# schematic.net
KiCad netlist of a schematic drawn in EAGLE
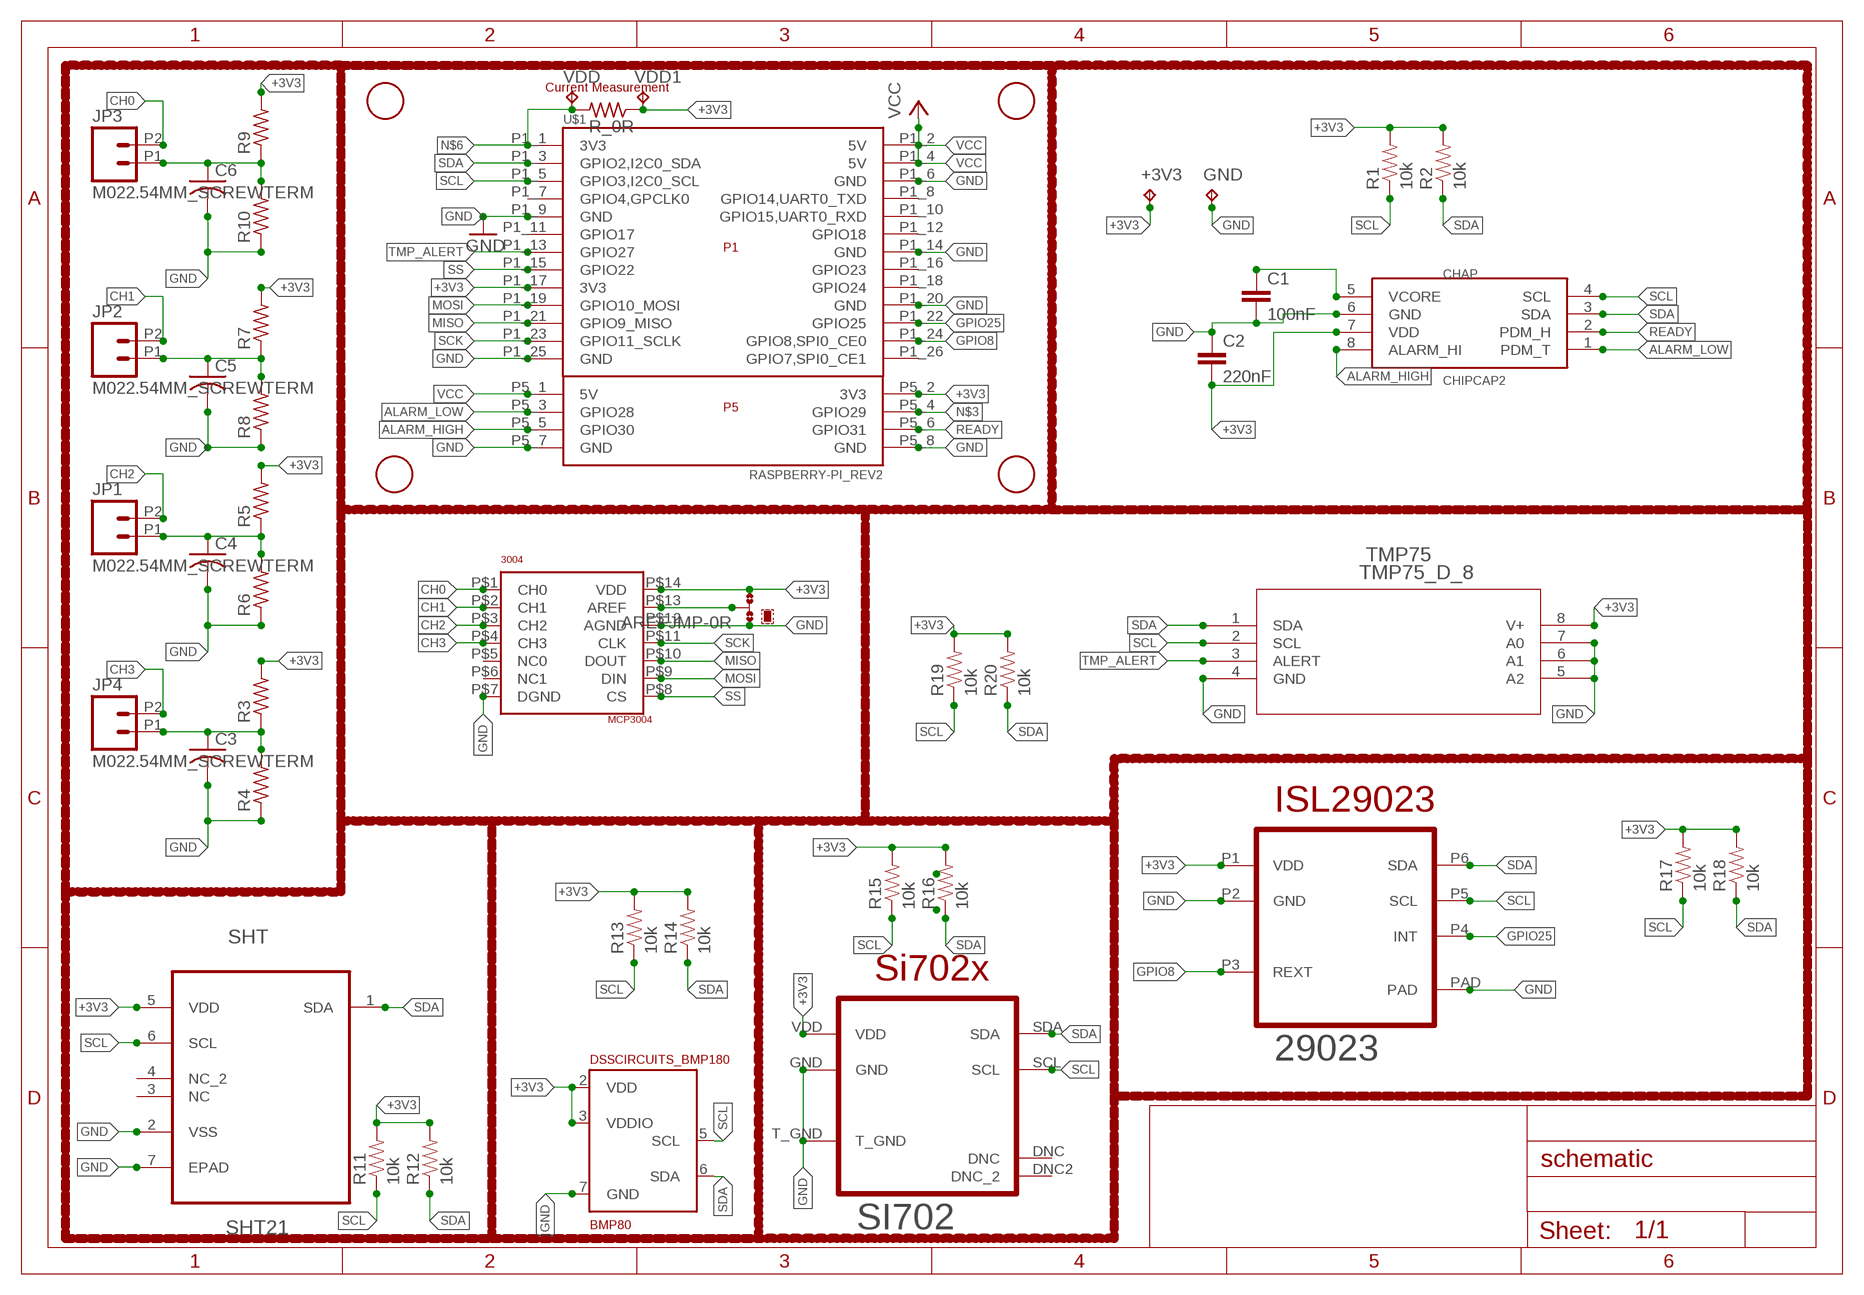
[diagram p0: schematic, sheet 1]

(export (version "E")
  (design (tool "Eeschema 10.0.6"))
  (components
    (comp (ref "+3V3")
      (value "TPTP20R")
      (footprint "eagle-import:TP20R")
      (libsource (lib "eagle-import") (part "TPTP20R"))
    )
    (comp (ref "3004")
      (value "MCP3004")
      (footprint "eagle-import:TSSOP14_4MM4")
      (libsource (lib "eagle-import") (part "MCP3004"))
    )
    (comp (ref "29023")
      (value "ISL29023")
      (footprint "eagle-import:ODFN6")
      (libsource (lib "eagle-import") (part "ISL29023"))
    )
    (comp (ref "AREFJMP")
      (value "0R-JUMPA")
      (footprint "eagle-import:A0R-JMP")
      (libsource (lib "eagle-import") (part "0R-JUMPA"))
    )
    (comp (ref "BMP80")
      (value "DSSCIRCUITS_BMP180")
      (footprint "eagle-import:DSSCIRCUITS_LGA7")
      (libsource (lib "eagle-import") (part "DSSCIRCUITS_BMP180"))
    )
    (comp (ref "C1")
      (value "100nF")
      (footprint "eagle-import:0402-CAP")
      (libsource (lib "eagle-import") (part "CAP0402-CAP"))
    )
    (comp (ref "C2")
      (value "220nF")
      (footprint "eagle-import:0402-CAP")
      (libsource (lib "eagle-import") (part "CAP0402-CAP"))
    )
    (comp (ref "C3")
      (value "C-USC0402")
      (footprint "eagle-import:C0402")
      (libsource (lib "eagle-import") (part "C-USC0402"))
    )
    (comp (ref "C4")
      (value "C-USC0402")
      (footprint "eagle-import:C0402")
      (libsource (lib "eagle-import") (part "C-USC0402"))
    )
    (comp (ref "C5")
      (value "C-USC0402")
      (footprint "eagle-import:C0402")
      (libsource (lib "eagle-import") (part "C-USC0402"))
    )
    (comp (ref "C6")
      (value "C-USC0402")
      (footprint "eagle-import:C0402")
      (libsource (lib "eagle-import") (part "C-USC0402"))
    )
    (comp (ref "CHAP")
      (value "CHIPCAP2")
      (footprint "eagle-import:CHIPCAP2")
      (libsource (lib "eagle-import") (part "CHIPCAP2"))
    )
    (comp (ref "GND")
      (value "TPTP20R")
      (footprint "eagle-import:TP20R")
      (libsource (lib "eagle-import") (part "TPTP20R"))
    )
    (comp (ref "JP1")
      (value "M022.54MM_SCREWTERM")
      (footprint "eagle-import:1X02_2.54_SCREWTERM")
      (libsource (lib "eagle-import") (part "M022.54MM_SCREWTERM"))
    )
    (comp (ref "JP2")
      (value "M022.54MM_SCREWTERM")
      (footprint "eagle-import:1X02_2.54_SCREWTERM")
      (libsource (lib "eagle-import") (part "M022.54MM_SCREWTERM"))
    )
    (comp (ref "JP3")
      (value "M022.54MM_SCREWTERM")
      (footprint "eagle-import:1X02_2.54_SCREWTERM")
      (libsource (lib "eagle-import") (part "M022.54MM_SCREWTERM"))
    )
    (comp (ref "JP4")
      (value "M022.54MM_SCREWTERM")
      (footprint "eagle-import:1X02_2.54_SCREWTERM")
      (libsource (lib "eagle-import") (part "M022.54MM_SCREWTERM"))
    )
    (comp (ref "R1")
      (value "10k")
      (footprint "eagle-import:0603-RES")
      (libsource (lib "eagle-import") (part "RESISTOR0603"))
    )
    (comp (ref "R2")
      (value "10k")
      (footprint "eagle-import:0603-RES")
      (libsource (lib "eagle-import") (part "RESISTOR0603"))
    )
    (comp (ref "R3")
      (value "R-US_R0402")
      (footprint "eagle-import:R0402")
      (libsource (lib "eagle-import") (part "R-US_R0402"))
    )
    (comp (ref "R4")
      (value "R-US_R0402")
      (footprint "eagle-import:R0402")
      (libsource (lib "eagle-import") (part "R-US_R0402"))
    )
    (comp (ref "R5")
      (value "R-US_R0402")
      (footprint "eagle-import:R0402")
      (libsource (lib "eagle-import") (part "R-US_R0402"))
    )
    (comp (ref "R6")
      (value "R-US_R0402")
      (footprint "eagle-import:R0402")
      (libsource (lib "eagle-import") (part "R-US_R0402"))
    )
    (comp (ref "R7")
      (value "R-US_R0402")
      (footprint "eagle-import:R0402")
      (libsource (lib "eagle-import") (part "R-US_R0402"))
    )
    (comp (ref "R8")
      (value "R-US_R0402")
      (footprint "eagle-import:R0402")
      (libsource (lib "eagle-import") (part "R-US_R0402"))
    )
    (comp (ref "R9")
      (value "R-US_R0402")
      (footprint "eagle-import:R0402")
      (libsource (lib "eagle-import") (part "R-US_R0402"))
    )
    (comp (ref "R10")
      (value "R-US_R0402")
      (footprint "eagle-import:R0402")
      (libsource (lib "eagle-import") (part "R-US_R0402"))
    )
    (comp (ref "R11")
      (value "10k")
      (footprint "eagle-import:0603-RES")
      (libsource (lib "eagle-import") (part "RESISTOR0603"))
    )
    (comp (ref "R12")
      (value "10k")
      (footprint "eagle-import:0603-RES")
      (libsource (lib "eagle-import") (part "RESISTOR0603"))
    )
    (comp (ref "R13")
      (value "10k")
      (footprint "eagle-import:0603-RES")
      (libsource (lib "eagle-import") (part "RESISTOR0603"))
    )
    (comp (ref "R14")
      (value "10k")
      (footprint "eagle-import:0603-RES")
      (libsource (lib "eagle-import") (part "RESISTOR0603"))
    )
    (comp (ref "R15")
      (value "10k")
      (footprint "eagle-import:0603-RES")
      (libsource (lib "eagle-import") (part "RESISTOR0603"))
    )
    (comp (ref "R16")
      (value "10k")
      (footprint "eagle-import:0603-RES")
      (libsource (lib "eagle-import") (part "RESISTOR0603"))
    )
    (comp (ref "R17")
      (value "10k")
      (footprint "eagle-import:0603-RES")
      (libsource (lib "eagle-import") (part "RESISTOR0603"))
    )
    (comp (ref "R18")
      (value "10k")
      (footprint "eagle-import:0603-RES")
      (libsource (lib "eagle-import") (part "RESISTOR0603"))
    )
    (comp (ref "R19")
      (value "10k")
      (footprint "eagle-import:0603-RES")
      (libsource (lib "eagle-import") (part "RESISTOR0603"))
    )
    (comp (ref "R20")
      (value "10k")
      (footprint "eagle-import:0603-RES")
      (libsource (lib "eagle-import") (part "RESISTOR0603"))
    )
    (comp (ref "R_0R")
      (value "R-US_R0402")
      (footprint "eagle-import:R0402")
      (libsource (lib "eagle-import") (part "R-US_R0402"))
    )
    (comp (ref "SHT")
      (value "SHT21")
      (footprint "eagle-import:DFN300X300X110-7N")
      (libsource (lib "eagle-import") (part "SHT21"))
    )
    (comp (ref "SI702")
      (value "SI702X")
      (footprint "eagle-import:DFN6")
      (libsource (lib "eagle-import") (part "SI702X"))
    )
    (comp (ref "TMP75")
      (value "TMP75_D_8")
      (footprint "eagle-import:D8")
      (fields
        (field (name "GENERIC_PART_NUMBER") "TMP75")
        (field (name "MANUFACTURER") "Texas Instruments")
        (field (name "MANUFACTURER_PART_NUMBER") "tmp75_d_8")
      )
      (libsource (lib "eagle-import") (part "TMP75_D_8"))
    )
    (comp (ref "U$1")
      (value "RASPBERRY-PI_REV2")
      (footprint "eagle-import:RASPBERRY-PI_REV2")
      (libsource (lib "eagle-import") (part "RASPBERRY-PI_REV2"))
    )
    (comp (ref "U$2")
      (value "FIDUCIAL")
      (footprint "eagle-import:FIDUCIAL_1MM")
      (libsource (lib "eagle-import") (part "FIDUCIAL"))
    )
    (comp (ref "U$3")
      (value "FIDUCIAL")
      (footprint "eagle-import:FIDUCIAL_1MM")
      (libsource (lib "eagle-import") (part "FIDUCIAL"))
    )
    (comp (ref "U$4")
      (value "FIDUCIAL")
      (footprint "eagle-import:FIDUCIAL_1MM")
      (libsource (lib "eagle-import") (part "FIDUCIAL"))
    )
    (comp (ref "U$5")
      (value "FIDUCIAL")
      (footprint "eagle-import:FIDUCIAL_1MM")
      (libsource (lib "eagle-import") (part "FIDUCIAL"))
    )
    (comp (ref "VDD")
      (value "TPTP20R")
      (footprint "eagle-import:TP20R")
      (libsource (lib "eagle-import") (part "TPTP20R"))
    )
    (comp (ref "VDD1")
      (value "TPTP20R")
      (footprint "eagle-import:TP20R")
      (libsource (lib "eagle-import") (part "TPTP20R"))
    )
  )
  (nets
    (net (code "1") (name "+3V3") (class "Default")
      (node (ref "+3V3") (pin "TP") (pinfunction "TP_TP") (pintype "input"))
      (node (ref "29023") (pin "P1") (pinfunction "VDD_P1") (pintype "bidirectional"))
      (node (ref "3004") (pin "P$14") (pinfunction "VDD_P$14") (pintype "bidirectional"))
      (node (ref "AREFJMP") (pin "3") (pinfunction "3_3") (pintype "passive"))
      (node (ref "BMP80") (pin "2") (pinfunction "VDD_2") (pintype "power_in"))
      (node (ref "BMP80") (pin "3") (pinfunction "VDDIO_3") (pintype "power_in"))
      (node (ref "C2") (pin "2") (pinfunction "2_2") (pintype "passive"))
      (node (ref "CHAP") (pin "7") (pinfunction "VDD_7") (pintype "bidirectional"))
      (node (ref "R1") (pin "2") (pinfunction "2_2") (pintype "passive"))
      (node (ref "R11") (pin "2") (pinfunction "2_2") (pintype "passive"))
      (node (ref "R12") (pin "2") (pinfunction "2_2") (pintype "passive"))
      (node (ref "R13") (pin "2") (pinfunction "2_2") (pintype "passive"))
      (node (ref "R14") (pin "2") (pinfunction "2_2") (pintype "passive"))
      (node (ref "R15") (pin "2") (pinfunction "2_2") (pintype "passive"))
      (node (ref "R16") (pin "2") (pinfunction "2_2") (pintype "passive"))
      (node (ref "R17") (pin "2") (pinfunction "2_2") (pintype "passive"))
      (node (ref "R18") (pin "2") (pinfunction "2_2") (pintype "passive"))
      (node (ref "R19") (pin "2") (pinfunction "2_2") (pintype "passive"))
      (node (ref "R2") (pin "2") (pinfunction "2_2") (pintype "passive"))
      (node (ref "R20") (pin "2") (pinfunction "2_2") (pintype "passive"))
      (node (ref "R3") (pin "2") (pinfunction "2_2") (pintype "passive"))
      (node (ref "R5") (pin "2") (pinfunction "2_2") (pintype "passive"))
      (node (ref "R7") (pin "2") (pinfunction "2_2") (pintype "passive"))
      (node (ref "R9") (pin "2") (pinfunction "2_2") (pintype "passive"))
      (node (ref "R_0R") (pin "1") (pinfunction "1_1") (pintype "passive"))
      (node (ref "SHT") (pin "5") (pinfunction "VDD_5") (pintype "power_in"))
      (node (ref "SI702") (pin "VDD") (pinfunction "VDD_VDD") (pintype "bidirectional"))
      (node (ref "TMP75") (pin "8") (pinfunction "V+_8") (pintype "power_in"))
      (node (ref "U$1") (pin "P1_17") (pinfunction "3V3_P1_17") (pintype "bidirectional"))
      (node (ref "U$1") (pin "P5_2") (pinfunction "3V3_P5_2") (pintype "bidirectional"))
      (node (ref "VDD1") (pin "TP") (pinfunction "TP_TP") (pintype "input"))
    )
    (net (code "2") (name "ALARM_HIGH") (class "Default")
      (node (ref "CHAP") (pin "8") (pinfunction "ALARM_HI_8") (pintype "bidirectional"))
      (node (ref "U$1") (pin "P5_5") (pinfunction "GPIO30_P5_5") (pintype "bidirectional"))
    )
    (net (code "3") (name "ALARM_LOW") (class "Default")
      (node (ref "CHAP") (pin "1") (pinfunction "PDM_T_1") (pintype "bidirectional"))
      (node (ref "U$1") (pin "P5_3") (pinfunction "GPIO28_P5_3") (pintype "bidirectional"))
    )
    (net (code "4") (name "CH0") (class "Default")
      (node (ref "3004") (pin "P$1") (pinfunction "CH0_P$1") (pintype "bidirectional"))
      (node (ref "JP3") (pin "P2") (pinfunction "2_P2") (pintype "passive"))
    )
    (net (code "5") (name "CH1") (class "Default")
      (node (ref "3004") (pin "P$2") (pinfunction "CH1_P$2") (pintype "bidirectional"))
      (node (ref "JP2") (pin "P2") (pinfunction "2_P2") (pintype "passive"))
    )
    (net (code "6") (name "CH2") (class "Default")
      (node (ref "3004") (pin "P$3") (pinfunction "CH2_P$3") (pintype "bidirectional"))
      (node (ref "JP1") (pin "P2") (pinfunction "2_P2") (pintype "passive"))
    )
    (net (code "7") (name "CH3") (class "Default")
      (node (ref "3004") (pin "P$4") (pinfunction "CH3_P$4") (pintype "bidirectional"))
      (node (ref "JP4") (pin "P2") (pinfunction "2_P2") (pintype "passive"))
    )
    (net (code "8") (name "GND") (class "Default")
      (node (ref "29023") (pin "P2") (pinfunction "GND_P2") (pintype "bidirectional"))
      (node (ref "29023") (pin "PAD") (pinfunction "PAD_PAD") (pintype "bidirectional"))
      (node (ref "3004") (pin "P$12") (pinfunction "AGND_P$12") (pintype "bidirectional"))
      (node (ref "3004") (pin "P$7") (pinfunction "DGND_P$7") (pintype "bidirectional"))
      (node (ref "AREFJMP") (pin "1") (pinfunction "1_1") (pintype "passive"))
      (node (ref "BMP80") (pin "7") (pinfunction "GND_7") (pintype "power_in"))
      (node (ref "C1") (pin "2") (pinfunction "2_2") (pintype "passive"))
      (node (ref "C2") (pin "1") (pinfunction "1_1") (pintype "passive"))
      (node (ref "C3") (pin "2") (pinfunction "2_2") (pintype "passive"))
      (node (ref "C4") (pin "2") (pinfunction "2_2") (pintype "passive"))
      (node (ref "C5") (pin "2") (pinfunction "2_2") (pintype "passive"))
      (node (ref "C6") (pin "2") (pinfunction "2_2") (pintype "passive"))
      (node (ref "CHAP") (pin "6") (pinfunction "GND_6") (pintype "bidirectional"))
      (node (ref "GND") (pin "TP") (pinfunction "TP_TP") (pintype "input"))
      (node (ref "R10") (pin "1") (pinfunction "1_1") (pintype "passive"))
      (node (ref "R4") (pin "1") (pinfunction "1_1") (pintype "passive"))
      (node (ref "R6") (pin "1") (pinfunction "1_1") (pintype "passive"))
      (node (ref "R8") (pin "1") (pinfunction "1_1") (pintype "passive"))
      (node (ref "SHT") (pin "2") (pinfunction "VSS_2") (pintype "power_in"))
      (node (ref "SHT") (pin "7") (pinfunction "EPAD_7") (pintype "passive"))
      (node (ref "SI702") (pin "GND") (pinfunction "GND_GND") (pintype "bidirectional"))
      (node (ref "SI702") (pin "T_GND") (pinfunction "T_GND_T_GND") (pintype "bidirectional"))
      (node (ref "TMP75") (pin "4") (pinfunction "GND_4") (pintype "power_in"))
      (node (ref "TMP75") (pin "5") (pinfunction "A2_5") (pintype "passive"))
      (node (ref "TMP75") (pin "6") (pinfunction "A1_6") (pintype "passive"))
      (node (ref "TMP75") (pin "7") (pinfunction "A0_7") (pintype "passive"))
      (node (ref "U$1") (pin "P1_14") (pinfunction "GND_P1_14") (pintype "bidirectional"))
      (node (ref "U$1") (pin "P1_20") (pinfunction "GND_P1_20") (pintype "bidirectional"))
      (node (ref "U$1") (pin "P1_25") (pinfunction "GND_P1_25") (pintype "bidirectional"))
      (node (ref "U$1") (pin "P1_6") (pinfunction "GND_P1_6") (pintype "bidirectional"))
      (node (ref "U$1") (pin "P1_9") (pinfunction "GND_P1_9") (pintype "bidirectional"))
      (node (ref "U$1") (pin "P5_7") (pinfunction "GND_P5_7") (pintype "bidirectional"))
      (node (ref "U$1") (pin "P5_8") (pinfunction "GND_P5_8") (pintype "bidirectional"))
    )
    (net (code "9") (name "GPIO8") (class "Default")
      (node (ref "29023") (pin "P3") (pinfunction "REXT_P3") (pintype "bidirectional"))
      (node (ref "U$1") (pin "P1_24") (pinfunction "GPIO8,SPI0_CE0_P1_24") (pintype "bidirectional"))
    )
    (net (code "10") (name "GPIO25") (class "Default")
      (node (ref "29023") (pin "P4") (pinfunction "INT_P4") (pintype "bidirectional"))
      (node (ref "U$1") (pin "P1_22") (pinfunction "GPIO25_P1_22") (pintype "bidirectional"))
    )
    (net (code "11") (name "MISO") (class "Default")
      (node (ref "3004") (pin "P$10") (pinfunction "DOUT_P$10") (pintype "bidirectional"))
      (node (ref "U$1") (pin "P1_21") (pinfunction "GPIO9_MISO_P1_21") (pintype "bidirectional"))
    )
    (net (code "12") (name "MOSI") (class "Default")
      (node (ref "3004") (pin "P$9") (pinfunction "DIN_P$9") (pintype "bidirectional"))
      (node (ref "U$1") (pin "P1_19") (pinfunction "GPIO10_MOSI_P1_19") (pintype "bidirectional"))
    )
    (net (code "13") (name "N$3") (class "Default")
      (node (ref "U$1") (pin "P5_4") (pinfunction "GPIO29_P5_4") (pintype "bidirectional"))
    )
    (net (code "14") (name "N$6") (class "Default")
      (node (ref "R_0R") (pin "2") (pinfunction "2_2") (pintype "passive"))
      (node (ref "U$1") (pin "P1_1") (pinfunction "3V3_P1_1") (pintype "bidirectional"))
      (node (ref "VDD") (pin "TP") (pinfunction "TP_TP") (pintype "input"))
    )
    (net (code "15") (name "Net-(3004-AREF)") (class "Default")
      (node (ref "3004") (pin "P$13") (pinfunction "AREF_P$13") (pintype "bidirectional"))
      (node (ref "AREFJMP") (pin "2") (pinfunction "2_2") (pintype "passive"))
    )
    (net (code "16") (name "Net-(CHAP-VCORE)") (class "Default")
      (node (ref "C1") (pin "1") (pinfunction "1_1") (pintype "passive"))
      (node (ref "CHAP") (pin "5") (pinfunction "VCORE_5") (pintype "bidirectional"))
    )
    (net (code "17") (name "Net-(JP1-1)") (class "Default")
      (node (ref "C4") (pin "1") (pinfunction "1_1") (pintype "passive"))
      (node (ref "JP1") (pin "P1") (pinfunction "1_P1") (pintype "passive"))
      (node (ref "R5") (pin "1") (pinfunction "1_1") (pintype "passive"))
      (node (ref "R6") (pin "2") (pinfunction "2_2") (pintype "passive"))
    )
    (net (code "18") (name "Net-(JP2-1)") (class "Default")
      (node (ref "C5") (pin "1") (pinfunction "1_1") (pintype "passive"))
      (node (ref "JP2") (pin "P1") (pinfunction "1_P1") (pintype "passive"))
      (node (ref "R7") (pin "1") (pinfunction "1_1") (pintype "passive"))
      (node (ref "R8") (pin "2") (pinfunction "2_2") (pintype "passive"))
    )
    (net (code "19") (name "Net-(JP3-1)") (class "Default")
      (node (ref "C6") (pin "1") (pinfunction "1_1") (pintype "passive"))
      (node (ref "JP3") (pin "P1") (pinfunction "1_P1") (pintype "passive"))
      (node (ref "R10") (pin "2") (pinfunction "2_2") (pintype "passive"))
      (node (ref "R9") (pin "1") (pinfunction "1_1") (pintype "passive"))
    )
    (net (code "20") (name "Net-(JP4-1)") (class "Default")
      (node (ref "C3") (pin "1") (pinfunction "1_1") (pintype "passive"))
      (node (ref "JP4") (pin "P1") (pinfunction "1_P1") (pintype "passive"))
      (node (ref "R3") (pin "1") (pinfunction "1_1") (pintype "passive"))
      (node (ref "R4") (pin "2") (pinfunction "2_2") (pintype "passive"))
    )
    (net (code "21") (name "READY") (class "Default")
      (node (ref "CHAP") (pin "2") (pinfunction "PDM_H_2") (pintype "bidirectional"))
      (node (ref "U$1") (pin "P5_6") (pinfunction "GPIO31_P5_6") (pintype "bidirectional"))
    )
    (net (code "22") (name "SCK") (class "Default")
      (node (ref "3004") (pin "P$11") (pinfunction "CLK_P$11") (pintype "bidirectional"))
      (node (ref "U$1") (pin "P1_23") (pinfunction "GPIO11_SCLK_P1_23") (pintype "bidirectional"))
    )
    (net (code "23") (name "SCL") (class "Default")
      (node (ref "29023") (pin "P5") (pinfunction "SCL_P5") (pintype "bidirectional"))
      (node (ref "BMP80") (pin "5") (pinfunction "SCL_5") (pintype "bidirectional"))
      (node (ref "CHAP") (pin "4") (pinfunction "SCL_4") (pintype "bidirectional"))
      (node (ref "R1") (pin "1") (pinfunction "1_1") (pintype "passive"))
      (node (ref "R11") (pin "1") (pinfunction "1_1") (pintype "passive"))
      (node (ref "R13") (pin "1") (pinfunction "1_1") (pintype "passive"))
      (node (ref "R15") (pin "1") (pinfunction "1_1") (pintype "passive"))
      (node (ref "R17") (pin "1") (pinfunction "1_1") (pintype "passive"))
      (node (ref "R19") (pin "1") (pinfunction "1_1") (pintype "passive"))
      (node (ref "SHT") (pin "6") (pinfunction "SCL_6") (pintype "input"))
      (node (ref "SI702") (pin "SCL") (pinfunction "SCL_SCL") (pintype "bidirectional"))
      (node (ref "TMP75") (pin "2") (pinfunction "SCL_2") (pintype "passive"))
      (node (ref "U$1") (pin "P1_5") (pinfunction "GPIO3,I2C0_SCL_P1_5") (pintype "bidirectional"))
    )
    (net (code "24") (name "SDA") (class "Default")
      (node (ref "29023") (pin "P6") (pinfunction "SDA_P6") (pintype "bidirectional"))
      (node (ref "BMP80") (pin "6") (pinfunction "SDA_6") (pintype "bidirectional"))
      (node (ref "CHAP") (pin "3") (pinfunction "SDA_3") (pintype "bidirectional"))
      (node (ref "R12") (pin "1") (pinfunction "1_1") (pintype "passive"))
      (node (ref "R14") (pin "1") (pinfunction "1_1") (pintype "passive"))
      (node (ref "R16") (pin "1") (pinfunction "1_1") (pintype "passive"))
      (node (ref "R18") (pin "1") (pinfunction "1_1") (pintype "passive"))
      (node (ref "R2") (pin "1") (pinfunction "1_1") (pintype "passive"))
      (node (ref "R20") (pin "1") (pinfunction "1_1") (pintype "passive"))
      (node (ref "SHT") (pin "1") (pinfunction "SDA_1") (pintype "bidirectional"))
      (node (ref "SI702") (pin "SDA") (pinfunction "SDA_SDA") (pintype "bidirectional"))
      (node (ref "TMP75") (pin "1") (pinfunction "SDA_1") (pintype "passive"))
      (node (ref "U$1") (pin "P1_3") (pinfunction "GPIO2,I2C0_SDA_P1_3") (pintype "bidirectional"))
    )
    (net (code "25") (name "SS") (class "Default")
      (node (ref "3004") (pin "P$8") (pinfunction "CS_P$8") (pintype "bidirectional"))
      (node (ref "U$1") (pin "P1_15") (pinfunction "GPIO22_P1_15") (pintype "bidirectional"))
    )
    (net (code "26") (name "TMP_ALERT") (class "Default")
      (node (ref "TMP75") (pin "3") (pinfunction "ALERT_3") (pintype "passive"))
      (node (ref "U$1") (pin "P1_13") (pinfunction "GPIO27_P1_13") (pintype "bidirectional"))
    )
    (net (code "27") (name "VCC") (class "Default")
      (node (ref "U$1") (pin "P1_2") (pinfunction "5V_P1_2") (pintype "bidirectional"))
      (node (ref "U$1") (pin "P1_4") (pinfunction "5V_P1_4") (pintype "bidirectional"))
      (node (ref "U$1") (pin "P5_1") (pinfunction "5V_P5_1") (pintype "bidirectional"))
    )
    (net (code "28") (name "unconnected-(3004-NC0-PadP$5)") (class "Default")
      (node (ref "3004") (pin "P$5") (pinfunction "NC0_P$5") (pintype "no_connect"))
    )
    (net (code "29") (name "unconnected-(3004-NC1-PadP$6)") (class "Default")
      (node (ref "3004") (pin "P$6") (pinfunction "NC1_P$6") (pintype "no_connect"))
    )
    (net (code "30") (name "unconnected-(BMP80-P$1-Pad1)") (class "Default")
      (node (ref "BMP80") (pin "1") (pinfunction "P$1_1") (pintype "no_connect"))
    )
    (net (code "31") (name "unconnected-(BMP80-P$2-Pad4)") (class "Default")
      (node (ref "BMP80") (pin "4") (pinfunction "P$2_4") (pintype "no_connect"))
    )
    (net (code "32") (name "unconnected-(SHT-NC-Pad3)") (class "Default")
      (node (ref "SHT") (pin "3") (pinfunction "NC_3") (pintype "no_connect"))
    )
    (net (code "33") (name "unconnected-(SHT-NC_2-Pad4)") (class "Default")
      (node (ref "SHT") (pin "4") (pinfunction "NC_2_4") (pintype "no_connect"))
    )
    (net (code "34") (name "unconnected-(SI702-DNC_2-PadDNC2)") (class "Default")
      (node (ref "SI702") (pin "DNC2") (pinfunction "DNC_2_DNC2") (pintype "bidirectional"))
    )
    (net (code "35") (name "unconnected-(SI702-PadDNC)") (class "Default")
      (node (ref "SI702") (pin "DNC") (pinfunction "DNC_DNC") (pintype "bidirectional"))
    )
    (net (code "36") (name "unconnected-(U$1-GPIO4,GPCLK0-PadP1_7)") (class "Default")
      (node (ref "U$1") (pin "P1_7") (pinfunction "GPIO4,GPCLK0_P1_7") (pintype "bidirectional"))
    )
    (net (code "37") (name "unconnected-(U$1-GPIO7,SPI0_CE1-PadP1_26)") (class "Default")
      (node (ref "U$1") (pin "P1_26") (pinfunction "GPIO7,SPI0_CE1_P1_26") (pintype "bidirectional"))
    )
    (net (code "38") (name "unconnected-(U$1-GPIO14,UART0_TXD-PadP1_8)") (class "Default")
      (node (ref "U$1") (pin "P1_8") (pinfunction "GPIO14,UART0_TXD_P1_8") (pintype "bidirectional"))
    )
    (net (code "39") (name "unconnected-(U$1-GPIO15,UART0_RXD-PadP1_10)") (class "Default")
      (node (ref "U$1") (pin "P1_10") (pinfunction "GPIO15,UART0_RXD_P1_10") (pintype "bidirectional"))
    )
    (net (code "40") (name "unconnected-(U$1-GPIO17-PadP1_11)") (class "Default")
      (node (ref "U$1") (pin "P1_11") (pinfunction "GPIO17_P1_11") (pintype "bidirectional"))
    )
    (net (code "41") (name "unconnected-(U$1-GPIO18-PadP1_12)") (class "Default")
      (node (ref "U$1") (pin "P1_12") (pinfunction "GPIO18_P1_12") (pintype "bidirectional"))
    )
    (net (code "42") (name "unconnected-(U$1-GPIO23-PadP1_16)") (class "Default")
      (node (ref "U$1") (pin "P1_16") (pinfunction "GPIO23_P1_16") (pintype "bidirectional"))
    )
    (net (code "43") (name "unconnected-(U$1-GPIO24-PadP1_18)") (class "Default")
      (node (ref "U$1") (pin "P1_18") (pinfunction "GPIO24_P1_18") (pintype "bidirectional"))
    )
  )
)
